# sheet_to_bcd.net
KiCad netlist of a schematic drawn in Altium Designer
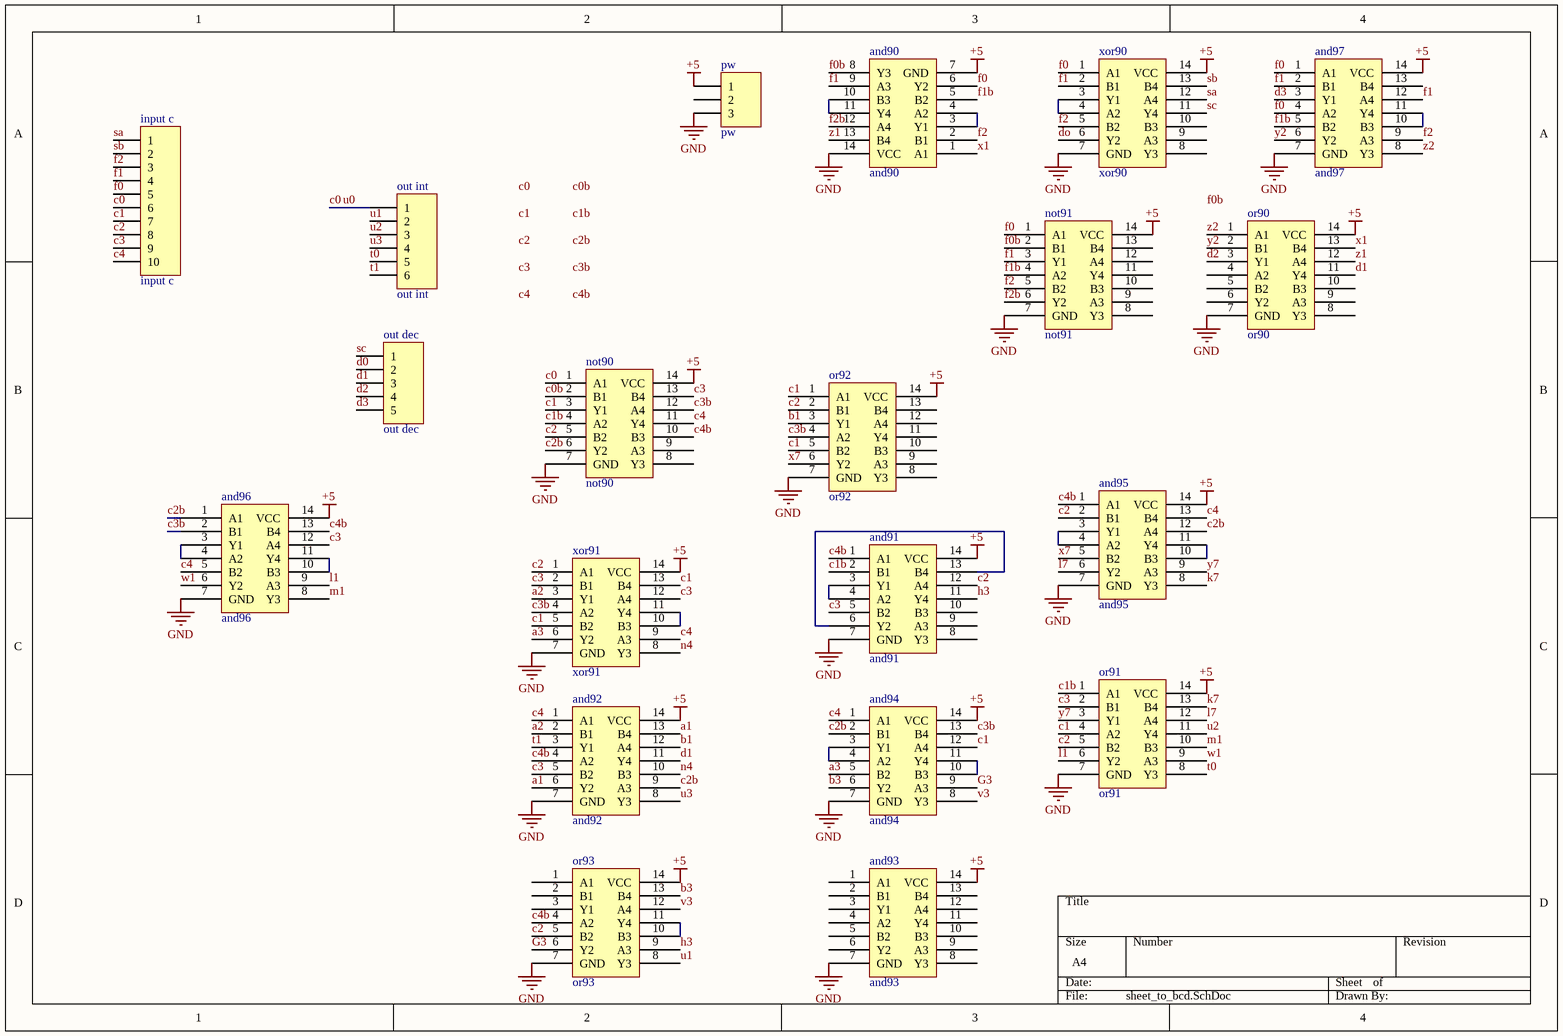
[diagram p0: sheet_to_bcd.SchDoc]

(export (version "E")
  (design (tool "Eeschema 10.0.6"))
  (components
    (comp (ref "and90")
      (value "and90")
      (footprint "PCBComponent_1")
      (libsource (lib "") (part "Component_1_1"))
    )
    (comp (ref "and91")
      (value "and91")
      (footprint "PCBComponent_1")
      (libsource (lib "Schlib3") (part "Component_1"))
    )
    (comp (ref "and92")
      (value "and92")
      (footprint "PCBComponent_1")
      (libsource (lib "Schlib3") (part "Component_1"))
    )
    (comp (ref "and93")
      (value "and93")
      (footprint "PCBComponent_1")
      (libsource (lib "Schlib3") (part "Component_1"))
    )
    (comp (ref "and94")
      (value "and94")
      (footprint "PCBComponent_1")
      (libsource (lib "Schlib3") (part "Component_1"))
    )
    (comp (ref "and95")
      (value "and95")
      (footprint "PCBComponent_1")
      (libsource (lib "Schlib3") (part "Component_1"))
    )
    (comp (ref "and96")
      (value "and96")
      (footprint "PCBComponent_1")
      (libsource (lib "Schlib3") (part "Component_1"))
    )
    (comp (ref "and97")
      (value "and97")
      (footprint "PCBComponent_1")
      (libsource (lib "Schlib2") (part "Component_1"))
    )
    (comp (ref "input c")
      (value "input c")
      (footprint "HDR1X10H")
      (description "Header, 10-Pin, Right Angle")
      (fields (field (name "PUBLISHER") "Altium Limited"))
      (libsource (lib "Miscellaneous Connectors") (part "Header 10H"))
    )
    (comp (ref "not90")
      (value "not90")
      (footprint "PCBComponent_1")
      (libsource (lib "Schlib3") (part "Component_1"))
    )
    (comp (ref "not91")
      (value "not91")
      (footprint "PCBComponent_1")
      (libsource (lib "Schlib2") (part "Component_1"))
    )
    (comp (ref "or90")
      (value "or90")
      (footprint "PCBComponent_1")
      (libsource (lib "Schlib2") (part "Component_1"))
    )
    (comp (ref "or91")
      (value "or91")
      (footprint "PCBComponent_1")
      (libsource (lib "Schlib3") (part "Component_1"))
    )
    (comp (ref "or92")
      (value "or92")
      (footprint "PCBComponent_1")
      (libsource (lib "Schlib3") (part "Component_1"))
    )
    (comp (ref "or93")
      (value "or93")
      (footprint "PCBComponent_1")
      (libsource (lib "Schlib3") (part "Component_1"))
    )
    (comp (ref "out dec")
      (value "out dec")
      (footprint "HDR1X5")
      (description "Header, 5-Pin")
      (fields (field (name "PUBLISHER") "Altium Limited"))
      (libsource (lib "Miscellaneous Connectors") (part "Header 5"))
    )
    (comp (ref "out int")
      (value "out int")
      (footprint "HDR1X6")
      (description "Header, 6-Pin")
      (fields (field (name "PUBLISHER") "Altium Limited"))
      (libsource (lib "Miscellaneous Connectors") (part "Header 6"))
    )
    (comp (ref "pw")
      (value "pw")
      (footprint "HDR1X3")
      (description "Header, 3-Pin")
      (fields (field (name "PUBLISHER") "Altium Limited"))
      (libsource (lib "Miscellaneous Connectors") (part "Header 3"))
    )
    (comp (ref "xor90")
      (value "xor90")
      (footprint "PCBComponent_1")
      (libsource (lib "Schlib2") (part "Component_1"))
    )
    (comp (ref "xor91")
      (value "xor91")
      (footprint "PCBComponent_1")
      (libsource (lib "Schlib3") (part "Component_1"))
    )
  )
  (nets
    (net (code "1") (name "+5") (class "Default")
      (node (ref "and90") (pin "7") (pinfunction "GND_7") (pintype "passive"))
      (node (ref "and91") (pin "14") (pinfunction "VCC_14") (pintype "passive"))
      (node (ref "and92") (pin "14") (pinfunction "VCC_14") (pintype "passive"))
      (node (ref "and93") (pin "14") (pinfunction "VCC_14") (pintype "passive"))
      (node (ref "and94") (pin "14") (pinfunction "VCC_14") (pintype "passive"))
      (node (ref "and95") (pin "14") (pinfunction "VCC_14") (pintype "passive"))
      (node (ref "and96") (pin "14") (pinfunction "VCC_14") (pintype "passive"))
      (node (ref "and97") (pin "14") (pinfunction "VCC_14") (pintype "passive"))
      (node (ref "not90") (pin "14") (pinfunction "VCC_14") (pintype "passive"))
      (node (ref "not91") (pin "14") (pinfunction "VCC_14") (pintype "passive"))
      (node (ref "or90") (pin "14") (pinfunction "VCC_14") (pintype "passive"))
      (node (ref "or91") (pin "14") (pinfunction "VCC_14") (pintype "passive"))
      (node (ref "or92") (pin "14") (pinfunction "VCC_14") (pintype "passive"))
      (node (ref "or93") (pin "14") (pinfunction "VCC_14") (pintype "passive"))
      (node (ref "pw") (pin "1") (pinfunction "1_1") (pintype "passive"))
      (node (ref "xor90") (pin "14") (pinfunction "VCC_14") (pintype "passive"))
      (node (ref "xor91") (pin "14") (pinfunction "VCC_14") (pintype "passive"))
    )
    (net (code "2") (name "/G3") (class "Default")
      (node (ref "and94") (pin "9") (pinfunction "A3_9") (pintype "passive"))
      (node (ref "or93") (pin "6") (pinfunction "Y2_6") (pintype "passive"))
    )
    (net (code "3") (name "/a1") (class "Default")
      (node (ref "and92") (pin "13") (pinfunction "B4_13") (pintype "passive"))
      (node (ref "and92") (pin "6") (pinfunction "Y2_6") (pintype "passive"))
    )
    (net (code "4") (name "/a2") (class "Default")
      (node (ref "and92") (pin "2") (pinfunction "B1_2") (pintype "passive"))
      (node (ref "xor91") (pin "3") (pinfunction "Y1_3") (pintype "passive"))
    )
    (net (code "5") (name "/a3") (class "Default")
      (node (ref "and94") (pin "5") (pinfunction "B2_5") (pintype "passive"))
      (node (ref "xor91") (pin "6") (pinfunction "Y2_6") (pintype "passive"))
    )
    (net (code "6") (name "/b1") (class "Default")
      (node (ref "and92") (pin "12") (pinfunction "A4_12") (pintype "passive"))
      (node (ref "or92") (pin "3") (pinfunction "Y1_3") (pintype "passive"))
    )
    (net (code "7") (name "/b3") (class "Default")
      (node (ref "and94") (pin "6") (pinfunction "Y2_6") (pintype "passive"))
      (node (ref "or93") (pin "13") (pinfunction "B4_13") (pintype "passive"))
    )
    (net (code "8") (name "/c0") (class "Default")
      (node (ref "input c") (pin "6") (pinfunction "6_6") (pintype "passive"))
      (node (ref "not90") (pin "1") (pinfunction "A1_1") (pintype "passive"))
      (node (ref "out int") (pin "1") (pinfunction "1_1") (pintype "passive"))
    )
    (net (code "9") (name "/c0b") (class "Default")
      (node (ref "not90") (pin "2") (pinfunction "B1_2") (pintype "passive"))
    )
    (net (code "10") (name "/c1") (class "Default")
      (node (ref "and94") (pin "12") (pinfunction "A4_12") (pintype "passive"))
      (node (ref "input c") (pin "7") (pinfunction "7_7") (pintype "passive"))
      (node (ref "not90") (pin "3") (pinfunction "Y1_3") (pintype "passive"))
      (node (ref "or91") (pin "4") (pinfunction "A2_4") (pintype "passive"))
      (node (ref "or92") (pin "1") (pinfunction "A1_1") (pintype "passive"))
      (node (ref "or92") (pin "5") (pinfunction "B2_5") (pintype "passive"))
      (node (ref "xor91") (pin "13") (pinfunction "B4_13") (pintype "passive"))
      (node (ref "xor91") (pin "5") (pinfunction "B2_5") (pintype "passive"))
    )
    (net (code "11") (name "/c1b") (class "Default")
      (node (ref "and91") (pin "2") (pinfunction "B1_2") (pintype "passive"))
      (node (ref "not90") (pin "4") (pinfunction "A2_4") (pintype "passive"))
      (node (ref "or91") (pin "1") (pinfunction "A1_1") (pintype "passive"))
    )
    (net (code "12") (name "/c2") (class "Default")
      (node (ref "and91") (pin "12") (pinfunction "A4_12") (pintype "passive"))
      (node (ref "and95") (pin "2") (pinfunction "B1_2") (pintype "passive"))
      (node (ref "input c") (pin "8") (pinfunction "8_8") (pintype "passive"))
      (node (ref "not90") (pin "5") (pinfunction "B2_5") (pintype "passive"))
      (node (ref "or91") (pin "5") (pinfunction "B2_5") (pintype "passive"))
      (node (ref "or92") (pin "2") (pinfunction "B1_2") (pintype "passive"))
      (node (ref "or93") (pin "5") (pinfunction "B2_5") (pintype "passive"))
      (node (ref "xor91") (pin "1") (pinfunction "A1_1") (pintype "passive"))
    )
    (net (code "13") (name "/c2b") (class "Default")
      (node (ref "and92") (pin "9") (pinfunction "A3_9") (pintype "passive"))
      (node (ref "and94") (pin "2") (pinfunction "B1_2") (pintype "passive"))
      (node (ref "and95") (pin "12") (pinfunction "A4_12") (pintype "passive"))
      (node (ref "and96") (pin "1") (pinfunction "A1_1") (pintype "passive"))
      (node (ref "not90") (pin "6") (pinfunction "Y2_6") (pintype "passive"))
    )
    (net (code "14") (name "/c3") (class "Default")
      (node (ref "and91") (pin "5") (pinfunction "B2_5") (pintype "passive"))
      (node (ref "and92") (pin "5") (pinfunction "B2_5") (pintype "passive"))
      (node (ref "and96") (pin "12") (pinfunction "A4_12") (pintype "passive"))
      (node (ref "input c") (pin "9") (pinfunction "9_9") (pintype "passive"))
      (node (ref "not90") (pin "13") (pinfunction "B4_13") (pintype "passive"))
      (node (ref "or91") (pin "2") (pinfunction "B1_2") (pintype "passive"))
      (node (ref "xor91") (pin "12") (pinfunction "A4_12") (pintype "passive"))
      (node (ref "xor91") (pin "2") (pinfunction "B1_2") (pintype "passive"))
    )
    (net (code "15") (name "/c3b") (class "Default")
      (node (ref "and94") (pin "13") (pinfunction "B4_13") (pintype "passive"))
      (node (ref "and96") (pin "2") (pinfunction "B1_2") (pintype "passive"))
      (node (ref "not90") (pin "12") (pinfunction "A4_12") (pintype "passive"))
      (node (ref "or92") (pin "4") (pinfunction "A2_4") (pintype "passive"))
      (node (ref "xor91") (pin "4") (pinfunction "A2_4") (pintype "passive"))
    )
    (net (code "16") (name "/c4") (class "Default")
      (node (ref "and92") (pin "1") (pinfunction "A1_1") (pintype "passive"))
      (node (ref "and94") (pin "1") (pinfunction "A1_1") (pintype "passive"))
      (node (ref "and95") (pin "13") (pinfunction "B4_13") (pintype "passive"))
      (node (ref "and96") (pin "5") (pinfunction "B2_5") (pintype "passive"))
      (node (ref "input c") (pin "10") (pinfunction "10_10") (pintype "passive"))
      (node (ref "not90") (pin "11") (pinfunction "Y4_11") (pintype "passive"))
      (node (ref "xor91") (pin "9") (pinfunction "A3_9") (pintype "passive"))
    )
    (net (code "17") (name "/c4b") (class "Default")
      (node (ref "and91") (pin "1") (pinfunction "A1_1") (pintype "passive"))
      (node (ref "and92") (pin "4") (pinfunction "A2_4") (pintype "passive"))
      (node (ref "and95") (pin "1") (pinfunction "A1_1") (pintype "passive"))
      (node (ref "and96") (pin "13") (pinfunction "B4_13") (pintype "passive"))
      (node (ref "not90") (pin "10") (pinfunction "B3_10") (pintype "passive"))
      (node (ref "or93") (pin "4") (pinfunction "A2_4") (pintype "passive"))
    )
    (net (code "18") (name "/d0") (class "Default")
      (node (ref "out dec") (pin "2") (pinfunction "2_2") (pintype "passive"))
    )
    (net (code "19") (name "/d1") (class "Default")
      (node (ref "and92") (pin "11") (pinfunction "Y4_11") (pintype "passive"))
      (node (ref "or90") (pin "11") (pinfunction "Y4_11") (pintype "passive"))
      (node (ref "out dec") (pin "3") (pinfunction "3_3") (pintype "passive"))
    )
    (net (code "20") (name "/d2") (class "Default")
      (node (ref "or90") (pin "3") (pinfunction "Y1_3") (pintype "passive"))
      (node (ref "out dec") (pin "4") (pinfunction "4_4") (pintype "passive"))
    )
    (net (code "21") (name "/d3") (class "Default")
      (node (ref "and97") (pin "3") (pinfunction "Y1_3") (pintype "passive"))
      (node (ref "out dec") (pin "5") (pinfunction "5_5") (pintype "passive"))
    )
    (net (code "22") (name "/do") (class "Default")
      (node (ref "xor90") (pin "6") (pinfunction "Y2_6") (pintype "passive"))
    )
    (net (code "23") (name "/f0") (class "Default")
      (node (ref "and90") (pin "6") (pinfunction "Y2_6") (pintype "passive"))
      (node (ref "and97") (pin "1") (pinfunction "A1_1") (pintype "passive"))
      (node (ref "and97") (pin "4") (pinfunction "A2_4") (pintype "passive"))
      (node (ref "input c") (pin "5") (pinfunction "5_5") (pintype "passive"))
      (node (ref "not91") (pin "1") (pinfunction "A1_1") (pintype "passive"))
      (node (ref "xor90") (pin "1") (pinfunction "A1_1") (pintype "passive"))
    )
    (net (code "24") (name "/f0b") (class "Default")
      (node (ref "and90") (pin "8") (pinfunction "Y3_8") (pintype "passive"))
      (node (ref "not91") (pin "2") (pinfunction "B1_2") (pintype "passive"))
    )
    (net (code "25") (name "/f1") (class "Default")
      (node (ref "and90") (pin "9") (pinfunction "A3_9") (pintype "passive"))
      (node (ref "and97") (pin "12") (pinfunction "A4_12") (pintype "passive"))
      (node (ref "and97") (pin "2") (pinfunction "B1_2") (pintype "passive"))
      (node (ref "input c") (pin "4") (pinfunction "4_4") (pintype "passive"))
      (node (ref "not91") (pin "3") (pinfunction "Y1_3") (pintype "passive"))
      (node (ref "xor90") (pin "2") (pinfunction "B1_2") (pintype "passive"))
    )
    (net (code "26") (name "/f1b") (class "Default")
      (node (ref "and90") (pin "5") (pinfunction "B2_5") (pintype "passive"))
      (node (ref "and97") (pin "5") (pinfunction "B2_5") (pintype "passive"))
      (node (ref "not91") (pin "4") (pinfunction "A2_4") (pintype "passive"))
    )
    (net (code "27") (name "/f2") (class "Default")
      (node (ref "and90") (pin "2") (pinfunction "B1_2") (pintype "passive"))
      (node (ref "and97") (pin "9") (pinfunction "A3_9") (pintype "passive"))
      (node (ref "input c") (pin "3") (pinfunction "3_3") (pintype "passive"))
      (node (ref "not91") (pin "5") (pinfunction "B2_5") (pintype "passive"))
      (node (ref "xor90") (pin "5") (pinfunction "B2_5") (pintype "passive"))
    )
    (net (code "28") (name "/f2b") (class "Default")
      (node (ref "and90") (pin "12") (pinfunction "A4_12") (pintype "passive"))
      (node (ref "not91") (pin "6") (pinfunction "Y2_6") (pintype "passive"))
    )
    (net (code "29") (name "/h3") (class "Default")
      (node (ref "and91") (pin "11") (pinfunction "Y4_11") (pintype "passive"))
      (node (ref "or93") (pin "9") (pinfunction "A3_9") (pintype "passive"))
    )
    (net (code "30") (name "/k7") (class "Default")
      (node (ref "and95") (pin "8") (pinfunction "Y3_8") (pintype "passive"))
      (node (ref "or91") (pin "13") (pinfunction "B4_13") (pintype "passive"))
    )
    (net (code "31") (name "/l1") (class "Default")
      (node (ref "and96") (pin "9") (pinfunction "A3_9") (pintype "passive"))
      (node (ref "or91") (pin "6") (pinfunction "Y2_6") (pintype "passive"))
    )
    (net (code "32") (name "/l7") (class "Default")
      (node (ref "and95") (pin "6") (pinfunction "Y2_6") (pintype "passive"))
      (node (ref "or91") (pin "12") (pinfunction "A4_12") (pintype "passive"))
    )
    (net (code "33") (name "/m1") (class "Default")
      (node (ref "and96") (pin "8") (pinfunction "Y3_8") (pintype "passive"))
      (node (ref "or91") (pin "10") (pinfunction "B3_10") (pintype "passive"))
    )
    (net (code "34") (name "/n4") (class "Default")
      (node (ref "and92") (pin "10") (pinfunction "B3_10") (pintype "passive"))
      (node (ref "xor91") (pin "8") (pinfunction "Y3_8") (pintype "passive"))
    )
    (net (code "35") (name "/sa") (class "Default")
      (node (ref "input c") (pin "1") (pinfunction "1_1") (pintype "passive"))
      (node (ref "xor90") (pin "12") (pinfunction "A4_12") (pintype "passive"))
    )
    (net (code "36") (name "/sb") (class "Default")
      (node (ref "input c") (pin "2") (pinfunction "2_2") (pintype "passive"))
      (node (ref "xor90") (pin "13") (pinfunction "B4_13") (pintype "passive"))
    )
    (net (code "37") (name "/sc") (class "Default")
      (node (ref "out dec") (pin "1") (pinfunction "1_1") (pintype "passive"))
      (node (ref "xor90") (pin "11") (pinfunction "Y4_11") (pintype "passive"))
    )
    (net (code "38") (name "/t0") (class "Default")
      (node (ref "or91") (pin "8") (pinfunction "Y3_8") (pintype "passive"))
      (node (ref "out int") (pin "5") (pinfunction "5_5") (pintype "passive"))
    )
    (net (code "39") (name "/t1") (class "Default")
      (node (ref "and92") (pin "3") (pinfunction "Y1_3") (pintype "passive"))
      (node (ref "out int") (pin "6") (pinfunction "6_6") (pintype "passive"))
    )
    (net (code "40") (name "/u1") (class "Default")
      (node (ref "or93") (pin "8") (pinfunction "Y3_8") (pintype "passive"))
      (node (ref "out int") (pin "2") (pinfunction "2_2") (pintype "passive"))
    )
    (net (code "41") (name "/u2") (class "Default")
      (node (ref "or91") (pin "11") (pinfunction "Y4_11") (pintype "passive"))
      (node (ref "out int") (pin "3") (pinfunction "3_3") (pintype "passive"))
    )
    (net (code "42") (name "/u3") (class "Default")
      (node (ref "and92") (pin "8") (pinfunction "Y3_8") (pintype "passive"))
      (node (ref "out int") (pin "4") (pinfunction "4_4") (pintype "passive"))
    )
    (net (code "43") (name "/v3") (class "Default")
      (node (ref "and94") (pin "8") (pinfunction "Y3_8") (pintype "passive"))
      (node (ref "or93") (pin "12") (pinfunction "A4_12") (pintype "passive"))
    )
    (net (code "44") (name "/w1") (class "Default")
      (node (ref "and96") (pin "6") (pinfunction "Y2_6") (pintype "passive"))
      (node (ref "or91") (pin "9") (pinfunction "A3_9") (pintype "passive"))
    )
    (net (code "45") (name "/x1") (class "Default")
      (node (ref "and90") (pin "1") (pinfunction "A1_1") (pintype "passive"))
      (node (ref "or90") (pin "13") (pinfunction "B4_13") (pintype "passive"))
    )
    (net (code "46") (name "/x7") (class "Default")
      (node (ref "and95") (pin "5") (pinfunction "B2_5") (pintype "passive"))
      (node (ref "or92") (pin "6") (pinfunction "Y2_6") (pintype "passive"))
    )
    (net (code "47") (name "/y2") (class "Default")
      (node (ref "and97") (pin "6") (pinfunction "Y2_6") (pintype "passive"))
      (node (ref "or90") (pin "2") (pinfunction "B1_2") (pintype "passive"))
    )
    (net (code "48") (name "/y7") (class "Default")
      (node (ref "and95") (pin "9") (pinfunction "A3_9") (pintype "passive"))
      (node (ref "or91") (pin "3") (pinfunction "Y1_3") (pintype "passive"))
    )
    (net (code "49") (name "/z1") (class "Default")
      (node (ref "and90") (pin "13") (pinfunction "B4_13") (pintype "passive"))
      (node (ref "or90") (pin "12") (pinfunction "A4_12") (pintype "passive"))
    )
    (net (code "50") (name "/z2") (class "Default")
      (node (ref "and97") (pin "8") (pinfunction "Y3_8") (pintype "passive"))
      (node (ref "or90") (pin "1") (pinfunction "A1_1") (pintype "passive"))
    )
    (net (code "51") (name "GND") (class "Default")
      (node (ref "and90") (pin "14") (pinfunction "VCC_14") (pintype "passive"))
      (node (ref "and91") (pin "7") (pinfunction "GND_7") (pintype "passive"))
      (node (ref "and92") (pin "7") (pinfunction "GND_7") (pintype "passive"))
      (node (ref "and93") (pin "7") (pinfunction "GND_7") (pintype "passive"))
      (node (ref "and94") (pin "7") (pinfunction "GND_7") (pintype "passive"))
      (node (ref "and95") (pin "7") (pinfunction "GND_7") (pintype "passive"))
      (node (ref "and96") (pin "7") (pinfunction "GND_7") (pintype "passive"))
      (node (ref "and97") (pin "7") (pinfunction "GND_7") (pintype "passive"))
      (node (ref "not90") (pin "7") (pinfunction "GND_7") (pintype "passive"))
      (node (ref "not91") (pin "7") (pinfunction "GND_7") (pintype "passive"))
      (node (ref "or90") (pin "7") (pinfunction "GND_7") (pintype "passive"))
      (node (ref "or91") (pin "7") (pinfunction "GND_7") (pintype "passive"))
      (node (ref "or92") (pin "7") (pinfunction "GND_7") (pintype "passive"))
      (node (ref "or93") (pin "7") (pinfunction "GND_7") (pintype "passive"))
      (node (ref "pw") (pin "3") (pinfunction "3_3") (pintype "passive"))
      (node (ref "xor90") (pin "7") (pinfunction "GND_7") (pintype "passive"))
      (node (ref "xor91") (pin "7") (pinfunction "GND_7") (pintype "passive"))
    )
    (net (code "52") (name "Net-(and90-A2)") (class "Default")
      (node (ref "and90") (pin "3") (pinfunction "Y1_3") (pintype "passive"))
      (node (ref "and90") (pin "4") (pinfunction "A2_4") (pintype "passive"))
    )
    (net (code "53") (name "Net-(and90-B3)") (class "Default")
      (node (ref "and90") (pin "10") (pinfunction "B3_10") (pintype "passive"))
      (node (ref "and90") (pin "11") (pinfunction "Y4_11") (pintype "passive"))
    )
    (net (code "54") (name "Net-(and91-A2)") (class "Default")
      (node (ref "and91") (pin "3") (pinfunction "Y1_3") (pintype "passive"))
      (node (ref "and91") (pin "4") (pinfunction "A2_4") (pintype "passive"))
    )
    (net (code "55") (name "Net-(and91-B4)") (class "Default")
      (node (ref "and91") (pin "13") (pinfunction "B4_13") (pintype "passive"))
      (node (ref "and91") (pin "6") (pinfunction "Y2_6") (pintype "passive"))
    )
    (net (code "56") (name "Net-(and94-A2)") (class "Default")
      (node (ref "and94") (pin "3") (pinfunction "Y1_3") (pintype "passive"))
      (node (ref "and94") (pin "4") (pinfunction "A2_4") (pintype "passive"))
    )
    (net (code "57") (name "Net-(and94-B3)") (class "Default")
      (node (ref "and94") (pin "10") (pinfunction "B3_10") (pintype "passive"))
      (node (ref "and94") (pin "11") (pinfunction "Y4_11") (pintype "passive"))
    )
    (net (code "58") (name "Net-(and95-A2)") (class "Default")
      (node (ref "and95") (pin "3") (pinfunction "Y1_3") (pintype "passive"))
      (node (ref "and95") (pin "4") (pinfunction "A2_4") (pintype "passive"))
    )
    (net (code "59") (name "Net-(and95-B3)") (class "Default")
      (node (ref "and95") (pin "10") (pinfunction "B3_10") (pintype "passive"))
      (node (ref "and95") (pin "11") (pinfunction "Y4_11") (pintype "passive"))
    )
    (net (code "60") (name "Net-(and96-A2)") (class "Default")
      (node (ref "and96") (pin "3") (pinfunction "Y1_3") (pintype "passive"))
      (node (ref "and96") (pin "4") (pinfunction "A2_4") (pintype "passive"))
    )
    (net (code "61") (name "Net-(and96-B3)") (class "Default")
      (node (ref "and96") (pin "10") (pinfunction "B3_10") (pintype "passive"))
      (node (ref "and96") (pin "11") (pinfunction "Y4_11") (pintype "passive"))
    )
    (net (code "62") (name "Net-(and97-B3)") (class "Default")
      (node (ref "and97") (pin "10") (pinfunction "B3_10") (pintype "passive"))
      (node (ref "and97") (pin "11") (pinfunction "Y4_11") (pintype "passive"))
    )
    (net (code "63") (name "Net-(or93-B3)") (class "Default")
      (node (ref "or93") (pin "10") (pinfunction "B3_10") (pintype "passive"))
      (node (ref "or93") (pin "11") (pinfunction "Y4_11") (pintype "passive"))
    )
    (net (code "64") (name "Net-(xor90-A2)") (class "Default")
      (node (ref "xor90") (pin "3") (pinfunction "Y1_3") (pintype "passive"))
      (node (ref "xor90") (pin "4") (pinfunction "A2_4") (pintype "passive"))
    )
    (net (code "65") (name "Net-(xor91-B3)") (class "Default")
      (node (ref "xor91") (pin "10") (pinfunction "B3_10") (pintype "passive"))
      (node (ref "xor91") (pin "11") (pinfunction "Y4_11") (pintype "passive"))
    )
    (net (code "66") (name "unconnected-(and91-A3-Pad9)") (class "Default")
      (node (ref "and91") (pin "9") (pinfunction "A3_9") (pintype "passive"))
    )
    (net (code "67") (name "unconnected-(and91-B3-Pad10)") (class "Default")
      (node (ref "and91") (pin "10") (pinfunction "B3_10") (pintype "passive"))
    )
    (net (code "68") (name "unconnected-(and91-Y3-Pad8)") (class "Default")
      (node (ref "and91") (pin "8") (pinfunction "Y3_8") (pintype "passive"))
    )
    (net (code "69") (name "unconnected-(and93-A1-Pad1)") (class "Default")
      (node (ref "and93") (pin "1") (pinfunction "A1_1") (pintype "passive"))
    )
    (net (code "70") (name "unconnected-(and93-A2-Pad4)") (class "Default")
      (node (ref "and93") (pin "4") (pinfunction "A2_4") (pintype "passive"))
    )
    (net (code "71") (name "unconnected-(and93-A3-Pad9)") (class "Default")
      (node (ref "and93") (pin "9") (pinfunction "A3_9") (pintype "passive"))
    )
    (net (code "72") (name "unconnected-(and93-A4-Pad12)") (class "Default")
      (node (ref "and93") (pin "12") (pinfunction "A4_12") (pintype "passive"))
    )
    (net (code "73") (name "unconnected-(and93-B1-Pad2)") (class "Default")
      (node (ref "and93") (pin "2") (pinfunction "B1_2") (pintype "passive"))
    )
    (net (code "74") (name "unconnected-(and93-B2-Pad5)") (class "Default")
      (node (ref "and93") (pin "5") (pinfunction "B2_5") (pintype "passive"))
    )
    (net (code "75") (name "unconnected-(and93-B3-Pad10)") (class "Default")
      (node (ref "and93") (pin "10") (pinfunction "B3_10") (pintype "passive"))
    )
    (net (code "76") (name "unconnected-(and93-B4-Pad13)") (class "Default")
      (node (ref "and93") (pin "13") (pinfunction "B4_13") (pintype "passive"))
    )
    (net (code "77") (name "unconnected-(and93-Y1-Pad3)") (class "Default")
      (node (ref "and93") (pin "3") (pinfunction "Y1_3") (pintype "passive"))
    )
    (net (code "78") (name "unconnected-(and93-Y2-Pad6)") (class "Default")
      (node (ref "and93") (pin "6") (pinfunction "Y2_6") (pintype "passive"))
    )
    (net (code "79") (name "unconnected-(and93-Y3-Pad8)") (class "Default")
      (node (ref "and93") (pin "8") (pinfunction "Y3_8") (pintype "passive"))
    )
    (net (code "80") (name "unconnected-(and93-Y4-Pad11)") (class "Default")
      (node (ref "and93") (pin "11") (pinfunction "Y4_11") (pintype "passive"))
    )
    (net (code "81") (name "unconnected-(and97-B4-Pad13)") (class "Default")
      (node (ref "and97") (pin "13") (pinfunction "B4_13") (pintype "passive"))
    )
    (net (code "82") (name "unconnected-(not90-A3-Pad9)") (class "Default")
      (node (ref "not90") (pin "9") (pinfunction "A3_9") (pintype "passive"))
    )
    (net (code "83") (name "unconnected-(not90-Y3-Pad8)") (class "Default")
      (node (ref "not90") (pin "8") (pinfunction "Y3_8") (pintype "passive"))
    )
    (net (code "84") (name "unconnected-(not91-A3-Pad9)") (class "Default")
      (node (ref "not91") (pin "9") (pinfunction "A3_9") (pintype "passive"))
    )
    (net (code "85") (name "unconnected-(not91-A4-Pad12)") (class "Default")
      (node (ref "not91") (pin "12") (pinfunction "A4_12") (pintype "passive"))
    )
    (net (code "86") (name "unconnected-(not91-B3-Pad10)") (class "Default")
      (node (ref "not91") (pin "10") (pinfunction "B3_10") (pintype "passive"))
    )
    (net (code "87") (name "unconnected-(not91-B4-Pad13)") (class "Default")
      (node (ref "not91") (pin "13") (pinfunction "B4_13") (pintype "passive"))
    )
    (net (code "88") (name "unconnected-(not91-Y3-Pad8)") (class "Default")
      (node (ref "not91") (pin "8") (pinfunction "Y3_8") (pintype "passive"))
    )
    (net (code "89") (name "unconnected-(not91-Y4-Pad11)") (class "Default")
      (node (ref "not91") (pin "11") (pinfunction "Y4_11") (pintype "passive"))
    )
    (net (code "90") (name "unconnected-(or90-A2-Pad4)") (class "Default")
      (node (ref "or90") (pin "4") (pinfunction "A2_4") (pintype "passive"))
    )
    (net (code "91") (name "unconnected-(or90-A3-Pad9)") (class "Default")
      (node (ref "or90") (pin "9") (pinfunction "A3_9") (pintype "passive"))
    )
    (net (code "92") (name "unconnected-(or90-B2-Pad5)") (class "Default")
      (node (ref "or90") (pin "5") (pinfunction "B2_5") (pintype "passive"))
    )
    (net (code "93") (name "unconnected-(or90-B3-Pad10)") (class "Default")
      (node (ref "or90") (pin "10") (pinfunction "B3_10") (pintype "passive"))
    )
    (net (code "94") (name "unconnected-(or90-Y2-Pad6)") (class "Default")
      (node (ref "or90") (pin "6") (pinfunction "Y2_6") (pintype "passive"))
    )
    (net (code "95") (name "unconnected-(or90-Y3-Pad8)") (class "Default")
      (node (ref "or90") (pin "8") (pinfunction "Y3_8") (pintype "passive"))
    )
    (net (code "96") (name "unconnected-(or92-A3-Pad9)") (class "Default")
      (node (ref "or92") (pin "9") (pinfunction "A3_9") (pintype "passive"))
    )
    (net (code "97") (name "unconnected-(or92-A4-Pad12)") (class "Default")
      (node (ref "or92") (pin "12") (pinfunction "A4_12") (pintype "passive"))
    )
    (net (code "98") (name "unconnected-(or92-B3-Pad10)") (class "Default")
      (node (ref "or92") (pin "10") (pinfunction "B3_10") (pintype "passive"))
    )
    (net (code "99") (name "unconnected-(or92-B4-Pad13)") (class "Default")
      (node (ref "or92") (pin "13") (pinfunction "B4_13") (pintype "passive"))
    )
    (net (code "100") (name "unconnected-(or92-Y3-Pad8)") (class "Default")
      (node (ref "or92") (pin "8") (pinfunction "Y3_8") (pintype "passive"))
    )
    (net (code "101") (name "unconnected-(or92-Y4-Pad11)") (class "Default")
      (node (ref "or92") (pin "11") (pinfunction "Y4_11") (pintype "passive"))
    )
    (net (code "102") (name "unconnected-(or93-A1-Pad1)") (class "Default")
      (node (ref "or93") (pin "1") (pinfunction "A1_1") (pintype "passive"))
    )
    (net (code "103") (name "unconnected-(or93-B1-Pad2)") (class "Default")
      (node (ref "or93") (pin "2") (pinfunction "B1_2") (pintype "passive"))
    )
    (net (code "104") (name "unconnected-(or93-Y1-Pad3)") (class "Default")
      (node (ref "or93") (pin "3") (pinfunction "Y1_3") (pintype "passive"))
    )
    (net (code "105") (name "unconnected-(pw-Pad2)") (class "Default")
      (node (ref "pw") (pin "2") (pinfunction "2_2") (pintype "passive"))
    )
    (net (code "106") (name "unconnected-(xor90-A3-Pad9)") (class "Default")
      (node (ref "xor90") (pin "9") (pinfunction "A3_9") (pintype "passive"))
    )
    (net (code "107") (name "unconnected-(xor90-B3-Pad10)") (class "Default")
      (node (ref "xor90") (pin "10") (pinfunction "B3_10") (pintype "passive"))
    )
    (net (code "108") (name "unconnected-(xor90-Y3-Pad8)") (class "Default")
      (node (ref "xor90") (pin "8") (pinfunction "Y3_8") (pintype "passive"))
    )
  )
)
